# 6_RgbLed.net
KiCad netlist of a schematic drawn in Altium Designer
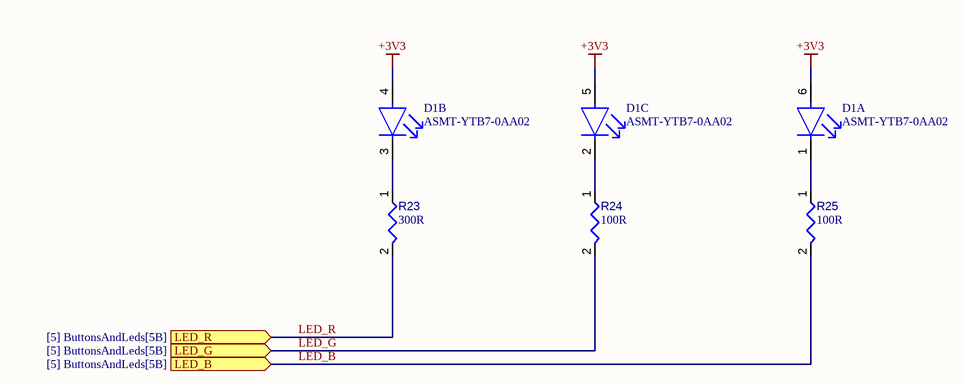
[diagram p0: [6] RgbLed.SchDoc]

(export (version "E")
  (design (tool "Eeschema 10.0.6"))
  (components
    (comp (ref "D1")
      (value "ASMT-YTB7-0AA02")
      (footprint "FP-PLCC-6-MFG")
      (description "LED Tri-Color Blue/Green/Red 469nm/529nm/623nm Chip LED 6-Pin PLCC T/R")
      (libsource (lib "UFCG - Universidade Federal de Campina Grande") (part "0f3d36aaa98356051a15b42400af8f3"))
    )
    (comp (ref "R23")
      (value "300R")
      (footprint "RESC0603(1608)_L")
      (description "Res Thick Film 0603 300 Ohm 5% 1/10W ±200ppm/°C Molded SMD Punched Carrier T/R")
      (fields (field (name "TOLERANCE") "5%") (field (name "Comment") "ERJ-3GEYJ301V"))
      (libsource (lib "UFCG - Universidade Federal de Campina Grande") (part "RES-2"))
    )
    (comp (ref "R24")
      (value "100R")
      (footprint "RESC0603(1608)_L")
      (description "SMD Chip Resistor, 100 Ohm, ï¿½ 1%, 100 mW, 0603 [1608 Metric], Thick Film, Precision")
      (fields (field (name "TOLERANCE") "1%") (field (name "Comment") "ERJ-3EKF1000V"))
      (libsource (lib "UFCG - Universidade Federal de Campina Grande") (part "RES-2"))
    )
    (comp (ref "R25")
      (value "100R")
      (footprint "RESC0603(1608)_L")
      (description "SMD Chip Resistor, 100 Ohm, ï¿½ 1%, 100 mW, 0603 [1608 Metric], Thick Film, Precision")
      (fields (field (name "TOLERANCE") "1%") (field (name "Comment") "ERJ-3EKF1000V"))
      (libsource (lib "UFCG - Universidade Federal de Campina Grande") (part "RES-2"))
    )
  )
  (nets
    (net (code "1") (name "+3V3") (class "Default")
      (node (ref "D1") (pin "4") (pinfunction "Anode(Red)_4") (pintype "passive"))
      (node (ref "D1") (pin "5") (pinfunction "Anode(Green)_5") (pintype "passive"))
      (node (ref "D1") (pin "6") (pinfunction "Anode(Blue)_6") (pintype "passive"))
    )
    (net (code "2") (name "/LED_B") (class "Default")
      (node (ref "R25") (pin "2") (pinfunction "2_2") (pintype "passive"))
    )
    (net (code "3") (name "/LED_G") (class "Default")
      (node (ref "R24") (pin "2") (pinfunction "2_2") (pintype "passive"))
    )
    (net (code "4") (name "/LED_R") (class "Default")
      (node (ref "R23") (pin "2") (pinfunction "2_2") (pintype "passive"))
    )
    (net (code "5") (name "Net-(D1A-Cathode(Blue))") (class "Default")
      (node (ref "D1") (pin "1") (pinfunction "Cathode(Blue)_1") (pintype "passive"))
      (node (ref "R25") (pin "1") (pinfunction "1_1") (pintype "passive"))
    )
    (net (code "6") (name "Net-(D1B-Cathode(Red))") (class "Default")
      (node (ref "D1") (pin "3") (pinfunction "Cathode(Red)_3") (pintype "passive"))
      (node (ref "R23") (pin "1") (pinfunction "1_1") (pintype "passive"))
    )
    (net (code "7") (name "Net-(D1C-Cathode(Green))") (class "Default")
      (node (ref "D1") (pin "2") (pinfunction "Cathode(Green)_2") (pintype "passive"))
      (node (ref "R24") (pin "1") (pinfunction "1_1") (pintype "passive"))
    )
  )
)
